# ir_rw_head.net
KiCad netlist of a schematic drawn in EAGLE
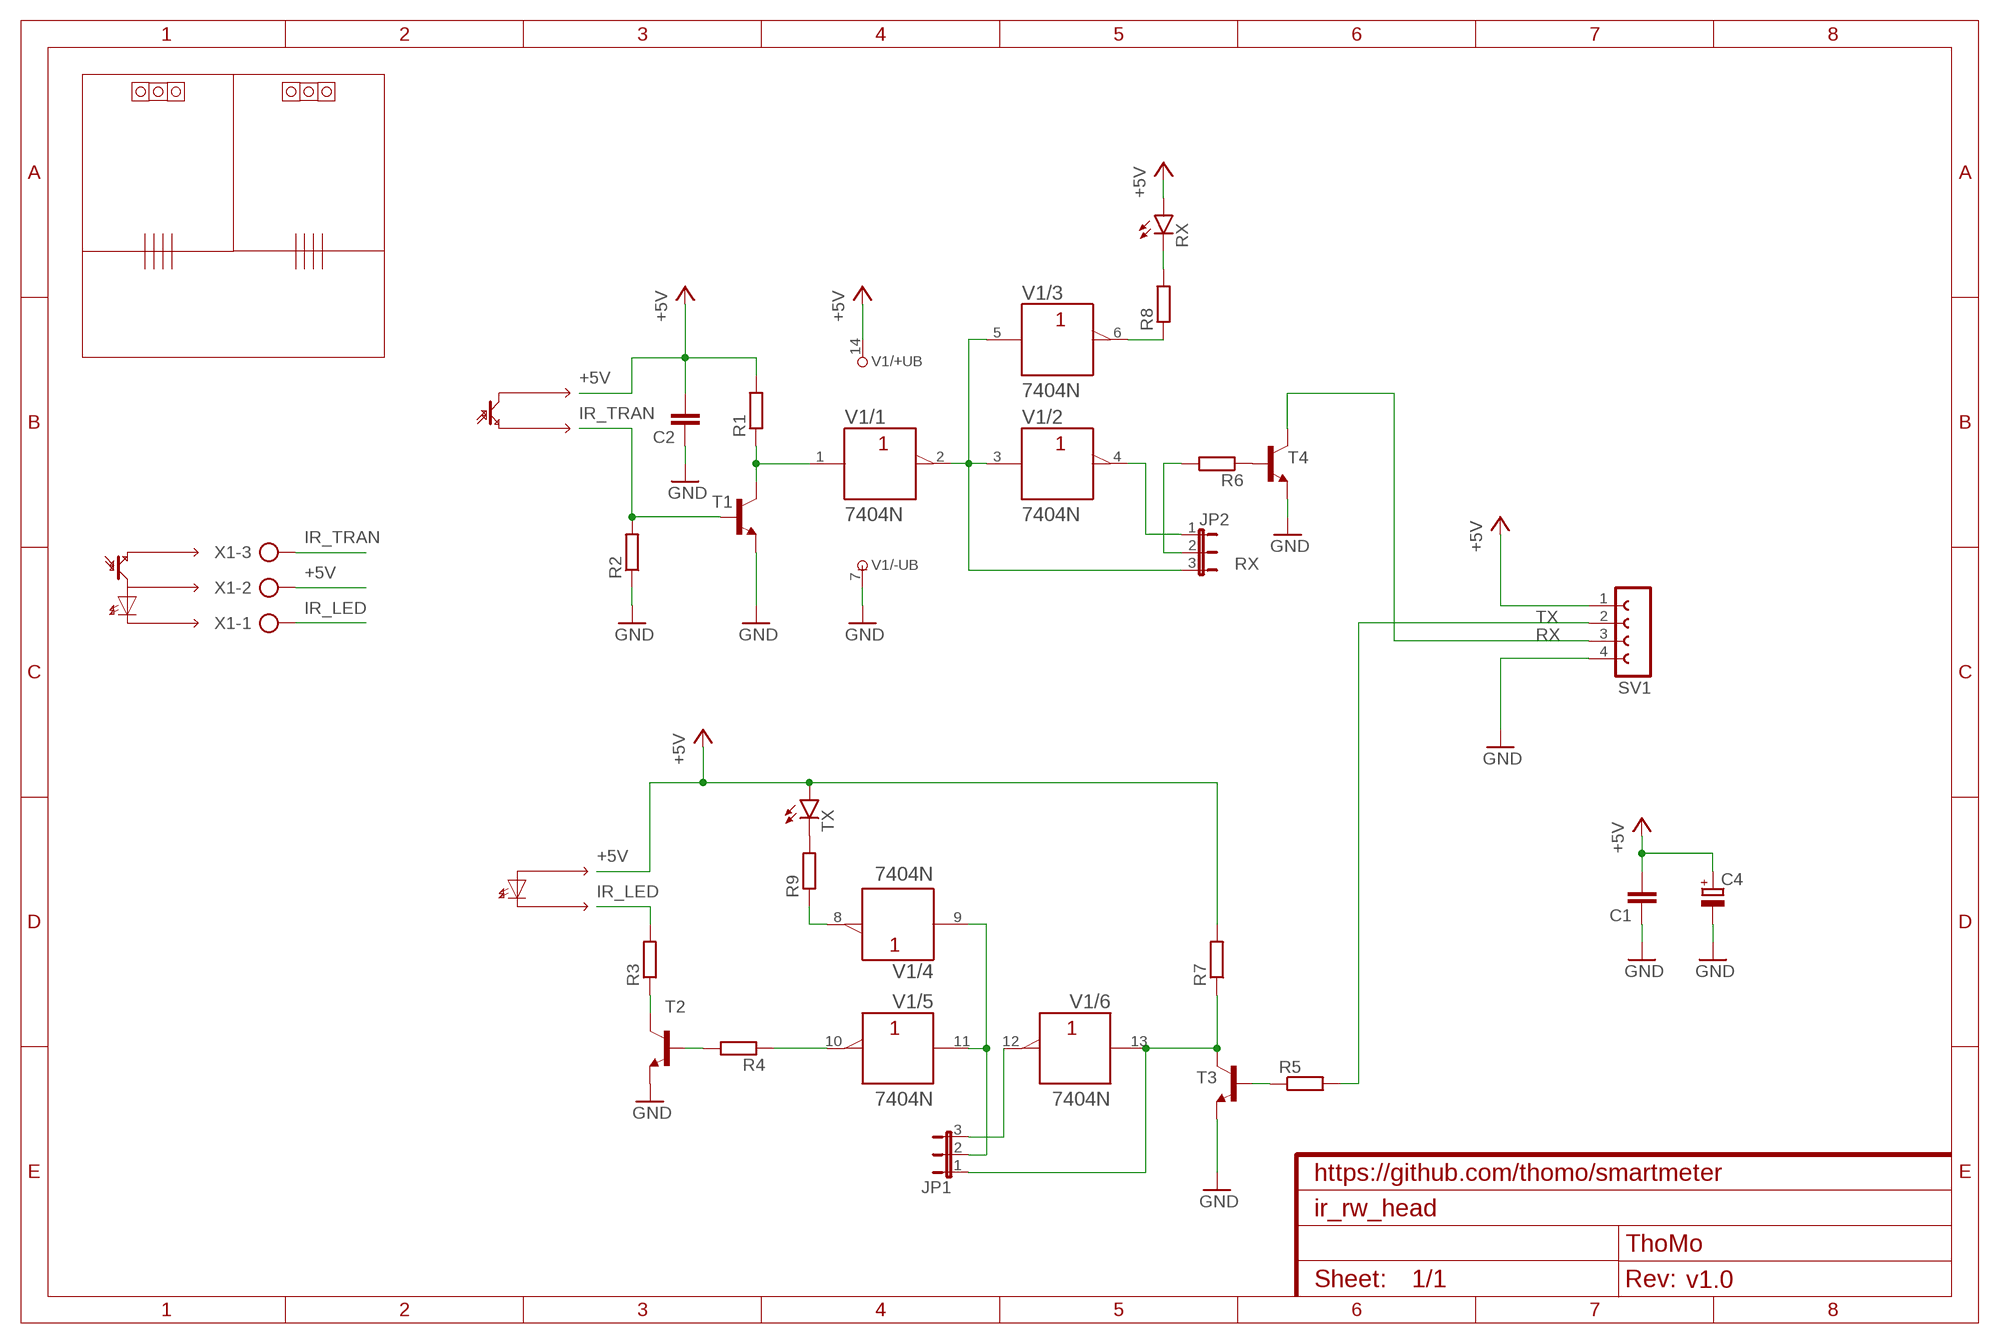
[diagram p0: schematic, sheet 1]

(export (version "E")
  (design (tool "Eeschema 10.0.6"))
  (components
    (comp (ref "C1")
      (value "C-EU050-030X075")
      (footprint "eagle-import:C050-030X075")
      (libsource (lib "eagle-import") (part "C-EU050-030X075"))
    )
    (comp (ref "C2")
      (value "C-EU050-030X075")
      (footprint "eagle-import:C050-030X075")
      (libsource (lib "eagle-import") (part "C-EU050-030X075"))
    )
    (comp (ref "C4")
      (value "CPOL-EUE2.5-7")
      (footprint "eagle-import:E2,5-7")
      (libsource (lib "eagle-import") (part "CPOL-EUE2.5-7"))
    )
    (comp (ref "JP1")
      (value "JP2E")
      (footprint "eagle-import:JP2")
      (libsource (lib "eagle-import") (part "JP2E"))
    )
    (comp (ref "JP2")
      (value "JP2E")
      (footprint "eagle-import:JP2")
      (libsource (lib "eagle-import") (part "JP2E"))
    )
    (comp (ref "R1")
      (value "R-EU_0207/10")
      (footprint "eagle-import:0207_10")
      (libsource (lib "eagle-import") (part "R-EU_0207/10"))
    )
    (comp (ref "R2")
      (value "R-EU_0207/10")
      (footprint "eagle-import:0207_10")
      (libsource (lib "eagle-import") (part "R-EU_0207/10"))
    )
    (comp (ref "R3")
      (value "R-EU_0207/10")
      (footprint "eagle-import:0207_10")
      (libsource (lib "eagle-import") (part "R-EU_0207/10"))
    )
    (comp (ref "R4")
      (value "R-EU_0207/10")
      (footprint "eagle-import:0207_10")
      (libsource (lib "eagle-import") (part "R-EU_0207/10"))
    )
    (comp (ref "R5")
      (value "R-EU_0207/10")
      (footprint "eagle-import:0207_10")
      (libsource (lib "eagle-import") (part "R-EU_0207/10"))
    )
    (comp (ref "R6")
      (value "R-EU_0207/10")
      (footprint "eagle-import:0207_10")
      (libsource (lib "eagle-import") (part "R-EU_0207/10"))
    )
    (comp (ref "R7")
      (value "R-EU_0207/10")
      (footprint "eagle-import:0207_10")
      (libsource (lib "eagle-import") (part "R-EU_0207/10"))
    )
    (comp (ref "R8")
      (value "R-EU_0207/10")
      (footprint "eagle-import:0207_10")
      (libsource (lib "eagle-import") (part "R-EU_0207/10"))
    )
    (comp (ref "R9")
      (value "R-EU_0207/10")
      (footprint "eagle-import:0207_10")
      (libsource (lib "eagle-import") (part "R-EU_0207/10"))
    )
    (comp (ref "RX")
      (value "LED5MM")
      (footprint "eagle-import:LED5MM")
      (libsource (lib "eagle-import") (part "LED5MM"))
    )
    (comp (ref "SV1")
      (value "FE04-1W")
      (footprint "eagle-import:FE04-1W")
      (libsource (lib "eagle-import") (part "FE04-1W"))
    )
    (comp (ref "T1")
      (value "-NPN-TO92-EBC")
      (footprint "eagle-import:TO92-EBC")
      (libsource (lib "eagle-import") (part "-NPN-TO92-EBC"))
    )
    (comp (ref "T2")
      (value "-NPN-TO92-EBC")
      (footprint "eagle-import:TO92-EBC")
      (libsource (lib "eagle-import") (part "-NPN-TO92-EBC"))
    )
    (comp (ref "T3")
      (value "-NPN-TO92-EBC")
      (footprint "eagle-import:TO92-EBC")
      (libsource (lib "eagle-import") (part "-NPN-TO92-EBC"))
    )
    (comp (ref "T4")
      (value "-NPN-TO92-EBC")
      (footprint "eagle-import:TO92-EBC")
      (libsource (lib "eagle-import") (part "-NPN-TO92-EBC"))
    )
    (comp (ref "TX")
      (value "LED5MM")
      (footprint "eagle-import:LED5MM")
      (libsource (lib "eagle-import") (part "LED5MM"))
    )
    (comp (ref "V1")
      (value "7404N")
      (footprint "eagle-import:DIL14")
      (libsource (lib "eagle-import") (part "7404N"))
    )
    (comp (ref "X1")
      (value "AK500/3")
      (footprint "eagle-import:AK500_3")
      (libsource (lib "eagle-import") (part "AK500/3"))
    )
  )
  (nets
    (net (code "1") (name "+5V") (class "Default")
      (node (ref "C1") (pin "2") (pinfunction "2_2") (pintype "passive"))
      (node (ref "C2") (pin "2") (pinfunction "2_2") (pintype "passive"))
      (node (ref "C4") (pin "+") (pinfunction "+_+") (pintype "passive"))
      (node (ref "R1") (pin "2") (pinfunction "2_2") (pintype "passive"))
      (node (ref "R7") (pin "2") (pinfunction "2_2") (pintype "passive"))
      (node (ref "RX") (pin "A") (pinfunction "A_A") (pintype "passive"))
      (node (ref "SV1") (pin "1") (pinfunction "1_1") (pintype "passive"))
      (node (ref "TX") (pin "A") (pinfunction "A_A") (pintype "passive"))
      (node (ref "V1") (pin "14") (pinfunction "+UB_14") (pintype "power_in"))
      (node (ref "X1") (pin "2") (pinfunction "KL_2") (pintype "passive"))
    )
    (net (code "2") (name "/IR_LED") (class "Default")
      (node (ref "R3") (pin "2") (pinfunction "2_2") (pintype "passive"))
      (node (ref "X1") (pin "1") (pinfunction "KL_1") (pintype "passive"))
    )
    (net (code "3") (name "/IR_TRAN") (class "Default")
      (node (ref "R2") (pin "2") (pinfunction "2_2") (pintype "passive"))
      (node (ref "T1") (pin "B") (pinfunction "B_B") (pintype "passive"))
      (node (ref "X1") (pin "3") (pinfunction "KL_3") (pintype "passive"))
    )
    (net (code "4") (name "/RX") (class "Default")
      (node (ref "SV1") (pin "3") (pinfunction "3_3") (pintype "passive"))
      (node (ref "T4") (pin "C") (pinfunction "C_C") (pintype "passive"))
    )
    (net (code "5") (name "/TX") (class "Default")
      (node (ref "R5") (pin "2") (pinfunction "2_2") (pintype "passive"))
      (node (ref "SV1") (pin "2") (pinfunction "2_2") (pintype "passive"))
    )
    (net (code "6") (name "GND") (class "Default")
      (node (ref "C1") (pin "1") (pinfunction "1_1") (pintype "passive"))
      (node (ref "C2") (pin "1") (pinfunction "1_1") (pintype "passive"))
      (node (ref "C4") (pin "-") (pinfunction "-_-") (pintype "passive"))
      (node (ref "R2") (pin "1") (pinfunction "1_1") (pintype "passive"))
      (node (ref "SV1") (pin "4") (pinfunction "4_4") (pintype "passive"))
      (node (ref "T1") (pin "E") (pinfunction "E_E") (pintype "passive"))
      (node (ref "T2") (pin "E") (pinfunction "E_E") (pintype "passive"))
      (node (ref "T3") (pin "E") (pinfunction "E_E") (pintype "passive"))
      (node (ref "T4") (pin "E") (pinfunction "E_E") (pintype "passive"))
      (node (ref "V1") (pin "7") (pinfunction "-UB_7") (pintype "power_in"))
    )
    (net (code "7") (name "Net-(JP2-Pad2)") (class "Default")
      (node (ref "JP2") (pin "2") (pinfunction "2_2") (pintype "passive"))
      (node (ref "R6") (pin "2") (pinfunction "2_2") (pintype "passive"))
    )
    (net (code "8") (name "Net-(R3-Pad1)") (class "Default")
      (node (ref "R3") (pin "1") (pinfunction "1_1") (pintype "passive"))
      (node (ref "T2") (pin "C") (pinfunction "C_C") (pintype "passive"))
    )
    (net (code "9") (name "Net-(R4-Pad2)") (class "Default")
      (node (ref "R4") (pin "2") (pinfunction "2_2") (pintype "passive"))
      (node (ref "T2") (pin "B") (pinfunction "B_B") (pintype "passive"))
    )
    (net (code "10") (name "Net-(R5-Pad1)") (class "Default")
      (node (ref "R5") (pin "1") (pinfunction "1_1") (pintype "passive"))
      (node (ref "T3") (pin "B") (pinfunction "B_B") (pintype "passive"))
    )
    (net (code "11") (name "Net-(R6-Pad1)") (class "Default")
      (node (ref "R6") (pin "1") (pinfunction "1_1") (pintype "passive"))
      (node (ref "T4") (pin "B") (pinfunction "B_B") (pintype "passive"))
    )
    (net (code "12") (name "Net-(RX-C)") (class "Default")
      (node (ref "R8") (pin "2") (pinfunction "2_2") (pintype "passive"))
      (node (ref "RX") (pin "K") (pinfunction "C_K") (pintype "passive"))
    )
    (net (code "13") (name "Net-(TX-C)") (class "Default")
      (node (ref "R9") (pin "2") (pinfunction "2_2") (pintype "passive"))
      (node (ref "TX") (pin "K") (pinfunction "C_K") (pintype "passive"))
    )
    (net (code "14") (name "Net-(V1C-A)") (class "Default")
      (node (ref "R1") (pin "1") (pinfunction "1_1") (pintype "passive"))
      (node (ref "T1") (pin "C") (pinfunction "C_C") (pintype "passive"))
      (node (ref "V1") (pin "1") (pinfunction "A_1") (pintype "input"))
    )
    (net (code "15") (name "Net-(V1C-Y)") (class "Default")
      (node (ref "JP2") (pin "3") (pinfunction "3_3") (pintype "passive"))
      (node (ref "V1") (pin "2") (pinfunction "Y_2") (pintype "output"))
      (node (ref "V1") (pin "3") (pinfunction "A_3") (pintype "input"))
      (node (ref "V1") (pin "5") (pinfunction "A_5") (pintype "input"))
    )
    (net (code "16") (name "Net-(V1D-Y)") (class "Default")
      (node (ref "JP2") (pin "1") (pinfunction "1_1") (pintype "passive"))
      (node (ref "V1") (pin "4") (pinfunction "Y_4") (pintype "output"))
    )
    (net (code "17") (name "Net-(V1E-Y)") (class "Default")
      (node (ref "R8") (pin "1") (pinfunction "1_1") (pintype "passive"))
      (node (ref "V1") (pin "6") (pinfunction "Y_6") (pintype "output"))
    )
    (net (code "18") (name "Net-(V1F-A)") (class "Default")
      (node (ref "JP1") (pin "2") (pinfunction "2_2") (pintype "passive"))
      (node (ref "V1") (pin "11") (pinfunction "A_11") (pintype "input"))
      (node (ref "V1") (pin "9") (pinfunction "A_9") (pintype "input"))
    )
    (net (code "19") (name "Net-(V1F-Y)") (class "Default")
      (node (ref "R9") (pin "1") (pinfunction "1_1") (pintype "passive"))
      (node (ref "V1") (pin "8") (pinfunction "Y_8") (pintype "output"))
    )
    (net (code "20") (name "Net-(V1G-Y)") (class "Default")
      (node (ref "R4") (pin "1") (pinfunction "1_1") (pintype "passive"))
      (node (ref "V1") (pin "10") (pinfunction "Y_10") (pintype "output"))
    )
    (net (code "21") (name "Net-(V1H-A)") (class "Default")
      (node (ref "JP1") (pin "1") (pinfunction "1_1") (pintype "passive"))
      (node (ref "R7") (pin "1") (pinfunction "1_1") (pintype "passive"))
      (node (ref "T3") (pin "C") (pinfunction "C_C") (pintype "passive"))
      (node (ref "V1") (pin "13") (pinfunction "A_13") (pintype "input"))
    )
    (net (code "22") (name "Net-(V1H-Y)") (class "Default")
      (node (ref "JP1") (pin "3") (pinfunction "3_3") (pintype "passive"))
      (node (ref "V1") (pin "12") (pinfunction "Y_12") (pintype "output"))
    )
  )
)
